# Glue.net
KiCad netlist of a schematic drawn in Altium Designer
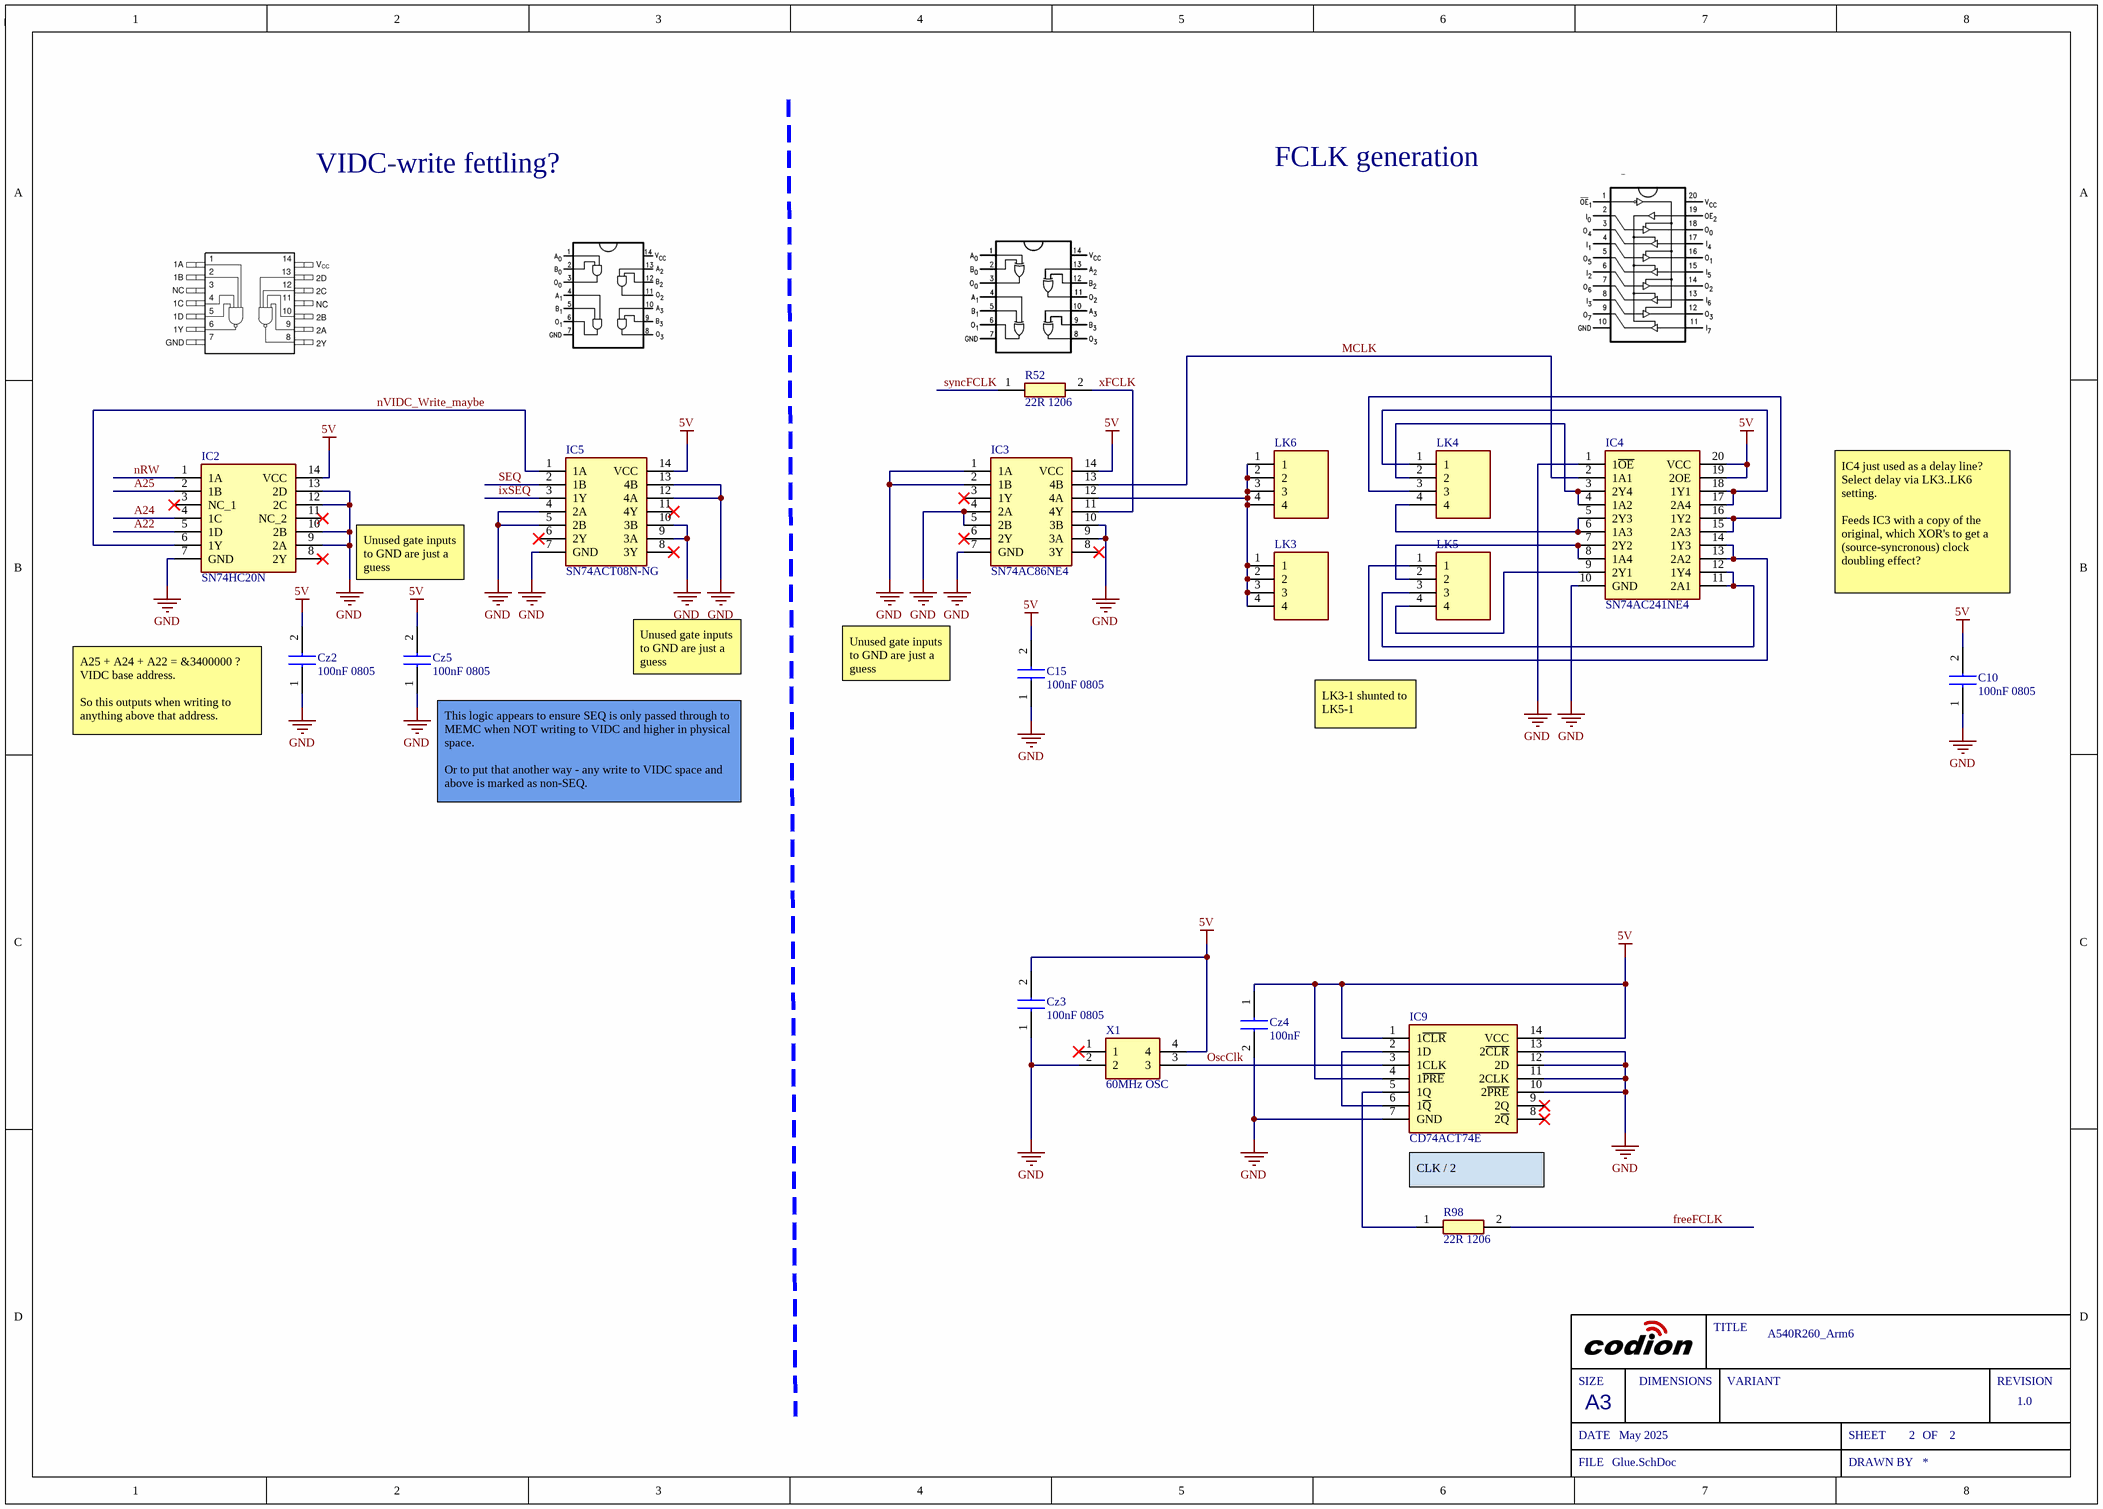
[diagram p0: Glue.SchDoc]

(export (version "E")
  (design (tool "Eeschema 10.0.6"))
  (components
    (comp (ref "C10")
      (value "100nF 0805")
      (footprint "SamacSys:CAPC2012X140N")
      (description "Capacitor")
      (fields
        (field (name "MANUFACTURER_PART_NUMBER") "C0805C104J4JACAUTO")
        (field (name "MOUSER PART NUMBER") "80-C0805C104J4JAUTO")
      )
      (libsource (lib "*") (part "C0805C104J4JACAUTO"))
    )
    (comp (ref "C15")
      (value "100nF 0805")
      (footprint "SamacSys:CAPC2012X140N")
      (description "Capacitor")
      (fields
        (field (name "MANUFACTURER_PART_NUMBER") "C0805C104J4JACAUTO")
        (field (name "MOUSER PART NUMBER") "80-C0805C104J4JAUTO")
      )
      (libsource (lib "*") (part "C0805C104J4JACAUTO"))
    )
    (comp (ref "Cz2")
      (value "100nF 0805")
      (footprint "SamacSys:CAPC2012X140N")
      (description "Capacitor")
      (fields
        (field (name "MANUFACTURER_PART_NUMBER") "C0805C104J4JACAUTO")
        (field (name "MOUSER PART NUMBER") "80-C0805C104J4JAUTO")
      )
      (libsource (lib "*") (part "C0805C104J4JACAUTO"))
    )
    (comp (ref "Cz3")
      (value "100nF 0805")
      (footprint "SamacSys:CAPC2012X140N")
      (description "Capacitor")
      (fields
        (field (name "MANUFACTURER_PART_NUMBER") "C0805C104J4JACAUTO")
        (field (name "MOUSER PART NUMBER") "80-C0805C104J4JAUTO")
      )
      (libsource (lib "*") (part "C0805C104J4JACAUTO"))
    )
    (comp (ref "Cz4")
      (value "100nF")
      (footprint "SamacSys:CAPC2012X145N")
      (description "Capacitor")
      (fields
        (field (name "MANUFACTURER_PART_NUMBER") "C2012X7R1H104K125AM")
        (field (name "MOUSER PART NUMBER") "810-C2012X7R1H104KT5")
      )
      (libsource (lib "*") (part "C2012X7R1H104K125AM"))
    )
    (comp (ref "Cz5")
      (value "100nF 0805")
      (footprint "SamacSys:CAPC2012X140N")
      (description "Capacitor")
      (fields
        (field (name "MANUFACTURER_PART_NUMBER") "C0805C104J4JACAUTO")
        (field (name "MOUSER PART NUMBER") "80-C0805C104J4JAUTO")
      )
      (libsource (lib "*") (part "C0805C104J4JACAUTO"))
    )
    (comp (ref "IC2")
      (value "SN74HC20N")
      (footprint "SamacSys:DIP794W53P254L1930H508Q14N")
      (description "Integrated Circuit")
      (fields (field (name "MOUSER PART NUMBER") "595-SN74HC20N"))
      (libsource (lib "*") (part "SN74HC20N"))
    )
    (comp (ref "IC3")
      (value "SN74AC86NE4")
      (footprint "SamacSys:DIP794W53P254L1930H508Q14N")
      (description "Integrated Circuit")
      (libsource (lib "*") (part "SN74AC86NE4"))
    )
    (comp (ref "IC4")
      (value "SN74AC241NE4")
      (footprint "SamacSys:DIP794W53P254L2540H508Q20N")
      (description "Integrated Circuit")
      (libsource (lib "*") (part "SN74AC241NE4"))
    )
    (comp (ref "IC5")
      (value "SN74ACT08N-NG")
      (footprint "SamacSys:DIP794W53P254L1930H508Q14N")
      (description "Integrated Circuit")
      (libsource (lib "*") (part "SN74ACT08N-NG"))
    )
    (comp (ref "IC9")
      (value "CD74ACT74E")
      (footprint "SamacSys:DIP794W53P254L1930H508Q14N")
      (description "Integrated Circuit")
      (fields (field (name "MOUSER PART NUMBER") "595-CD74ACT74E"))
      (libsource (lib "*") (part "CD74ACT74E"))
    )
    (comp (ref "LK3")
      (value "PREC004SAAN-RC")
      (footprint "SamacSys:HDRV4W64P0X254_1X4_1016X254X854P")
      (description "Connector")
      (libsource (lib "*") (part "PREC004SAAN-RC"))
    )
    (comp (ref "LK4")
      (value "PREC004SAAN-RC")
      (footprint "SamacSys:HDRV4W64P0X254_1X4_1016X254X854P")
      (description "Connector")
      (libsource (lib "*") (part "PREC004SAAN-RC"))
    )
    (comp (ref "LK5")
      (value "PREC004SAAN-RC")
      (footprint "SamacSys:HDRV4W64P0X254_1X4_1016X254X854P")
      (description "Connector")
      (libsource (lib "*") (part "PREC004SAAN-RC"))
    )
    (comp (ref "LK6")
      (value "PREC004SAAN-RC")
      (footprint "SamacSys:HDRV4W64P0X254_1X4_1016X254X854P")
      (description "Connector")
      (libsource (lib "*") (part "PREC004SAAN-RC"))
    )
    (comp (ref "R52")
      (value "22R 1206")
      (footprint "SamacSys:ERJUP8")
      (description "Resistor")
      (fields (field (name "MANUFACTURER_PART_NUMBER") "ERJ-UP8D22R0V"))
      (libsource (lib "*") (part "ERJ-UP8D22R0V"))
    )
    (comp (ref "R98")
      (value "22R 1206")
      (footprint "SamacSys:ERJUP8")
      (description "Resistor")
      (fields (field (name "MANUFACTURER_PART_NUMBER") "ERJ-UP8D22R0V"))
      (libsource (lib "*") (part "ERJ-UP8D22R0V"))
    )
    (comp (ref "X1")
      (value "60MHz OSC")
      (footprint "SamacSys:DIPS762W56P1524L1778H241Q4N")
      (fields
        (field (name "MANUFACTURER_PART_NUMBER") "1107741")
        (field (name "MOUSER PART NUMBER") "535-1107741")
      )
      (libsource (lib "*") (part "1107741"))
    )
  )
  (nets
    (net (code "1") (name "/A22") (class "Default")
      (node (ref "IC2") (pin "5") (pinfunction "1D_5") (pintype "passive"))
    )
    (net (code "2") (name "/A24") (class "Default")
      (node (ref "IC2") (pin "4") (pinfunction "1C_4") (pintype "passive"))
    )
    (net (code "3") (name "/A25") (class "Default")
      (node (ref "IC2") (pin "2") (pinfunction "1B_2") (pintype "passive"))
    )
    (net (code "4") (name "/MCLK") (class "Default")
      (node (ref "IC3") (pin "13") (pinfunction "4B_13") (pintype "passive"))
      (node (ref "IC4") (pin "2") (pinfunction "1A1_2") (pintype "passive"))
    )
    (net (code "5") (name "/OscClk") (class "Default")
      (node (ref "IC9") (pin "3") (pinfunction "1CLK_3") (pintype "passive"))
      (node (ref "X1") (pin "3") (pinfunction "3_3") (pintype "passive"))
    )
    (net (code "6") (name "/SEQ") (class "Default")
      (node (ref "IC5") (pin "2") (pinfunction "1B_2") (pintype "passive"))
    )
    (net (code "7") (name "/freeFCLK") (class "Default")
      (node (ref "R98") (pin "2") (pinfunction "2_2") (pintype "passive"))
    )
    (net (code "8") (name "/ixSEQ") (class "Default")
      (node (ref "IC5") (pin "3") (pinfunction "1Y_3") (pintype "passive"))
    )
    (net (code "9") (name "/nRW") (class "Default")
      (node (ref "IC2") (pin "1") (pinfunction "1A_1") (pintype "passive"))
    )
    (net (code "10") (name "/nVIDC_Write_maybe") (class "Default")
      (node (ref "IC2") (pin "6") (pinfunction "1Y_6") (pintype "passive"))
      (node (ref "IC5") (pin "1") (pinfunction "1A_1") (pintype "passive"))
    )
    (net (code "11") (name "/syncFCLK") (class "Default")
      (node (ref "R52") (pin "1") (pinfunction "1_1") (pintype "passive"))
    )
    (net (code "12") (name "/xFCLK") (class "Default")
      (node (ref "IC3") (pin "11") (pinfunction "4Y_11") (pintype "passive"))
      (node (ref "R52") (pin "2") (pinfunction "2_2") (pintype "passive"))
    )
    (net (code "13") (name "5V") (class "Default")
      (node (ref "C10") (pin "2") (pinfunction "2_2") (pintype "passive"))
      (node (ref "C15") (pin "2") (pinfunction "2_2") (pintype "passive"))
      (node (ref "Cz2") (pin "2") (pinfunction "2_2") (pintype "passive"))
      (node (ref "Cz3") (pin "2") (pinfunction "2_2") (pintype "passive"))
      (node (ref "Cz4") (pin "1") (pinfunction "1_1") (pintype "passive"))
      (node (ref "Cz5") (pin "2") (pinfunction "2_2") (pintype "passive"))
      (node (ref "IC2") (pin "14") (pinfunction "VCC_14") (pintype "passive"))
      (node (ref "IC3") (pin "14") (pinfunction "VCC_14") (pintype "passive"))
      (node (ref "IC4") (pin "19") (pinfunction "2OE_19") (pintype "passive"))
      (node (ref "IC4") (pin "20") (pinfunction "VCC_20") (pintype "passive"))
      (node (ref "IC5") (pin "14") (pinfunction "VCC_14") (pintype "passive"))
      (node (ref "IC9") (pin "1") (pinfunction "1~{CLR}_1") (pintype "passive"))
      (node (ref "IC9") (pin "14") (pinfunction "VCC_14") (pintype "passive"))
      (node (ref "IC9") (pin "4") (pinfunction "1~{PRE}_4") (pintype "passive"))
      (node (ref "X1") (pin "4") (pinfunction "4_4") (pintype "passive"))
    )
    (net (code "14") (name "GND") (class "Default")
      (node (ref "C10") (pin "1") (pinfunction "1_1") (pintype "passive"))
      (node (ref "C15") (pin "1") (pinfunction "1_1") (pintype "passive"))
      (node (ref "Cz2") (pin "1") (pinfunction "1_1") (pintype "passive"))
      (node (ref "Cz3") (pin "1") (pinfunction "1_1") (pintype "passive"))
      (node (ref "Cz4") (pin "2") (pinfunction "2_2") (pintype "passive"))
      (node (ref "Cz5") (pin "1") (pinfunction "1_1") (pintype "passive"))
      (node (ref "IC2") (pin "10") (pinfunction "2B_10") (pintype "passive"))
      (node (ref "IC2") (pin "12") (pinfunction "2C_12") (pintype "passive"))
      (node (ref "IC2") (pin "13") (pinfunction "2D_13") (pintype "passive"))
      (node (ref "IC2") (pin "7") (pinfunction "GND_7") (pintype "passive"))
      (node (ref "IC2") (pin "9") (pinfunction "2A_9") (pintype "passive"))
      (node (ref "IC3") (pin "1") (pinfunction "1A_1") (pintype "passive"))
      (node (ref "IC3") (pin "10") (pinfunction "3B_10") (pintype "passive"))
      (node (ref "IC3") (pin "2") (pinfunction "1B_2") (pintype "passive"))
      (node (ref "IC3") (pin "4") (pinfunction "2A_4") (pintype "passive"))
      (node (ref "IC3") (pin "5") (pinfunction "2B_5") (pintype "passive"))
      (node (ref "IC3") (pin "7") (pinfunction "GND_7") (pintype "passive"))
      (node (ref "IC3") (pin "9") (pinfunction "3A_9") (pintype "passive"))
      (node (ref "IC4") (pin "1") (pinfunction "1~{OE}_1") (pintype "passive"))
      (node (ref "IC4") (pin "10") (pinfunction "GND_10") (pintype "passive"))
      (node (ref "IC5") (pin "10") (pinfunction "3B_10") (pintype "passive"))
      (node (ref "IC5") (pin "12") (pinfunction "4A_12") (pintype "passive"))
      (node (ref "IC5") (pin "13") (pinfunction "4B_13") (pintype "passive"))
      (node (ref "IC5") (pin "4") (pinfunction "2A_4") (pintype "passive"))
      (node (ref "IC5") (pin "5") (pinfunction "2B_5") (pintype "passive"))
      (node (ref "IC5") (pin "7") (pinfunction "GND_7") (pintype "passive"))
      (node (ref "IC5") (pin "9") (pinfunction "3A_9") (pintype "passive"))
      (node (ref "IC9") (pin "10") (pinfunction "2~{PRE}_10") (pintype "passive"))
      (node (ref "IC9") (pin "11") (pinfunction "2CLK_11") (pintype "passive"))
      (node (ref "IC9") (pin "12") (pinfunction "2D_12") (pintype "passive"))
      (node (ref "IC9") (pin "13") (pinfunction "2~{CLR}_13") (pintype "passive"))
      (node (ref "IC9") (pin "7") (pinfunction "GND_7") (pintype "passive"))
      (node (ref "X1") (pin "2") (pinfunction "2_2") (pintype "passive"))
    )
    (net (code "15") (name "Net-(IC3-4A)") (class "Default")
      (node (ref "IC3") (pin "12") (pinfunction "4A_12") (pintype "passive"))
      (node (ref "LK3") (pin "1") (pinfunction "1_1") (pintype "passive"))
      (node (ref "LK3") (pin "2") (pinfunction "2_2") (pintype "passive"))
      (node (ref "LK3") (pin "3") (pinfunction "3_3") (pintype "passive"))
      (node (ref "LK3") (pin "4") (pinfunction "4_4") (pintype "passive"))
      (node (ref "LK6") (pin "1") (pinfunction "1_1") (pintype "passive"))
      (node (ref "LK6") (pin "2") (pinfunction "2_2") (pintype "passive"))
      (node (ref "LK6") (pin "3") (pinfunction "3_3") (pintype "passive"))
      (node (ref "LK6") (pin "4") (pinfunction "4_4") (pintype "passive"))
    )
    (net (code "16") (name "Net-(IC4-1A2)") (class "Default")
      (node (ref "IC4") (pin "3") (pinfunction "2Y4_3") (pintype "passive"))
      (node (ref "IC4") (pin "4") (pinfunction "1A2_4") (pintype "passive"))
      (node (ref "LK4") (pin "2") (pinfunction "2_2") (pintype "passive"))
    )
    (net (code "17") (name "Net-(IC4-1A3)") (class "Default")
      (node (ref "IC4") (pin "5") (pinfunction "2Y3_5") (pintype "passive"))
      (node (ref "IC4") (pin "6") (pinfunction "1A3_6") (pintype "passive"))
      (node (ref "LK4") (pin "4") (pinfunction "4_4") (pintype "passive"))
    )
    (net (code "18") (name "Net-(IC4-1A4)") (class "Default")
      (node (ref "IC4") (pin "7") (pinfunction "2Y2_7") (pintype "passive"))
      (node (ref "IC4") (pin "8") (pinfunction "1A4_8") (pintype "passive"))
      (node (ref "LK5") (pin "2") (pinfunction "2_2") (pintype "passive"))
    )
    (net (code "19") (name "Net-(IC4-1Y1)") (class "Default")
      (node (ref "IC4") (pin "17") (pinfunction "2A4_17") (pintype "passive"))
      (node (ref "IC4") (pin "18") (pinfunction "1Y1_18") (pintype "passive"))
      (node (ref "LK4") (pin "1") (pinfunction "1_1") (pintype "passive"))
    )
    (net (code "20") (name "Net-(IC4-1Y2)") (class "Default")
      (node (ref "IC4") (pin "15") (pinfunction "2A3_15") (pintype "passive"))
      (node (ref "IC4") (pin "16") (pinfunction "1Y2_16") (pintype "passive"))
      (node (ref "LK4") (pin "3") (pinfunction "3_3") (pintype "passive"))
    )
    (net (code "21") (name "Net-(IC4-1Y3)") (class "Default")
      (node (ref "IC4") (pin "13") (pinfunction "2A2_13") (pintype "passive"))
      (node (ref "IC4") (pin "14") (pinfunction "1Y3_14") (pintype "passive"))
      (node (ref "LK5") (pin "1") (pinfunction "1_1") (pintype "passive"))
    )
    (net (code "22") (name "Net-(IC4-1Y4)") (class "Default")
      (node (ref "IC4") (pin "11") (pinfunction "2A1_11") (pintype "passive"))
      (node (ref "IC4") (pin "12") (pinfunction "1Y4_12") (pintype "passive"))
      (node (ref "LK5") (pin "3") (pinfunction "3_3") (pintype "passive"))
    )
    (net (code "23") (name "Net-(IC4-2Y1)") (class "Default")
      (node (ref "IC4") (pin "9") (pinfunction "2Y1_9") (pintype "passive"))
      (node (ref "LK5") (pin "4") (pinfunction "4_4") (pintype "passive"))
    )
    (net (code "24") (name "Net-(IC9-1D)") (class "Default")
      (node (ref "IC9") (pin "2") (pinfunction "1D_2") (pintype "passive"))
      (node (ref "IC9") (pin "6") (pinfunction "1~{Q}_6") (pintype "passive"))
    )
    (net (code "25") (name "Net-(IC9-1Q)") (class "Default")
      (node (ref "IC9") (pin "5") (pinfunction "1Q_5") (pintype "passive"))
      (node (ref "R98") (pin "1") (pinfunction "1_1") (pintype "passive"))
    )
    (net (code "26") (name "unconnected-(IC2-2Y-Pad8)") (class "Default")
      (node (ref "IC2") (pin "8") (pinfunction "2Y_8") (pintype "passive+no_connect"))
    )
    (net (code "27") (name "unconnected-(IC2-NC_1-Pad3)") (class "Default")
      (node (ref "IC2") (pin "3") (pinfunction "NC_1_3") (pintype "passive+no_connect"))
    )
    (net (code "28") (name "unconnected-(IC2-NC_2-Pad11)") (class "Default")
      (node (ref "IC2") (pin "11") (pinfunction "NC_2_11") (pintype "passive+no_connect"))
    )
    (net (code "29") (name "unconnected-(IC3-1Y-Pad3)") (class "Default")
      (node (ref "IC3") (pin "3") (pinfunction "1Y_3") (pintype "passive+no_connect"))
    )
    (net (code "30") (name "unconnected-(IC3-2Y-Pad6)") (class "Default")
      (node (ref "IC3") (pin "6") (pinfunction "2Y_6") (pintype "passive+no_connect"))
    )
    (net (code "31") (name "unconnected-(IC3-3Y-Pad8)") (class "Default")
      (node (ref "IC3") (pin "8") (pinfunction "3Y_8") (pintype "passive+no_connect"))
    )
    (net (code "32") (name "unconnected-(IC5-2Y-Pad6)") (class "Default")
      (node (ref "IC5") (pin "6") (pinfunction "2Y_6") (pintype "passive+no_connect"))
    )
    (net (code "33") (name "unconnected-(IC5-3Y-Pad8)") (class "Default")
      (node (ref "IC5") (pin "8") (pinfunction "3Y_8") (pintype "passive+no_connect"))
    )
    (net (code "34") (name "unconnected-(IC5-4Y-Pad11)") (class "Default")
      (node (ref "IC5") (pin "11") (pinfunction "4Y_11") (pintype "passive+no_connect"))
    )
    (net (code "35") (name "unconnected-(IC9-2Q-Pad9)") (class "Default")
      (node (ref "IC9") (pin "9") (pinfunction "2Q_9") (pintype "passive+no_connect"))
    )
    (net (code "36") (name "unconnected-(IC9-2~{Q}-Pad8)") (class "Default")
      (node (ref "IC9") (pin "8") (pinfunction "2~{Q}_8") (pintype "passive+no_connect"))
    )
    (net (code "37") (name "unconnected-(X1-Pad1)") (class "Default")
      (node (ref "X1") (pin "1") (pinfunction "1_1") (pintype "passive+no_connect"))
    )
  )
)
